# MCU.net
KiCad netlist of a schematic drawn in Altium Designer
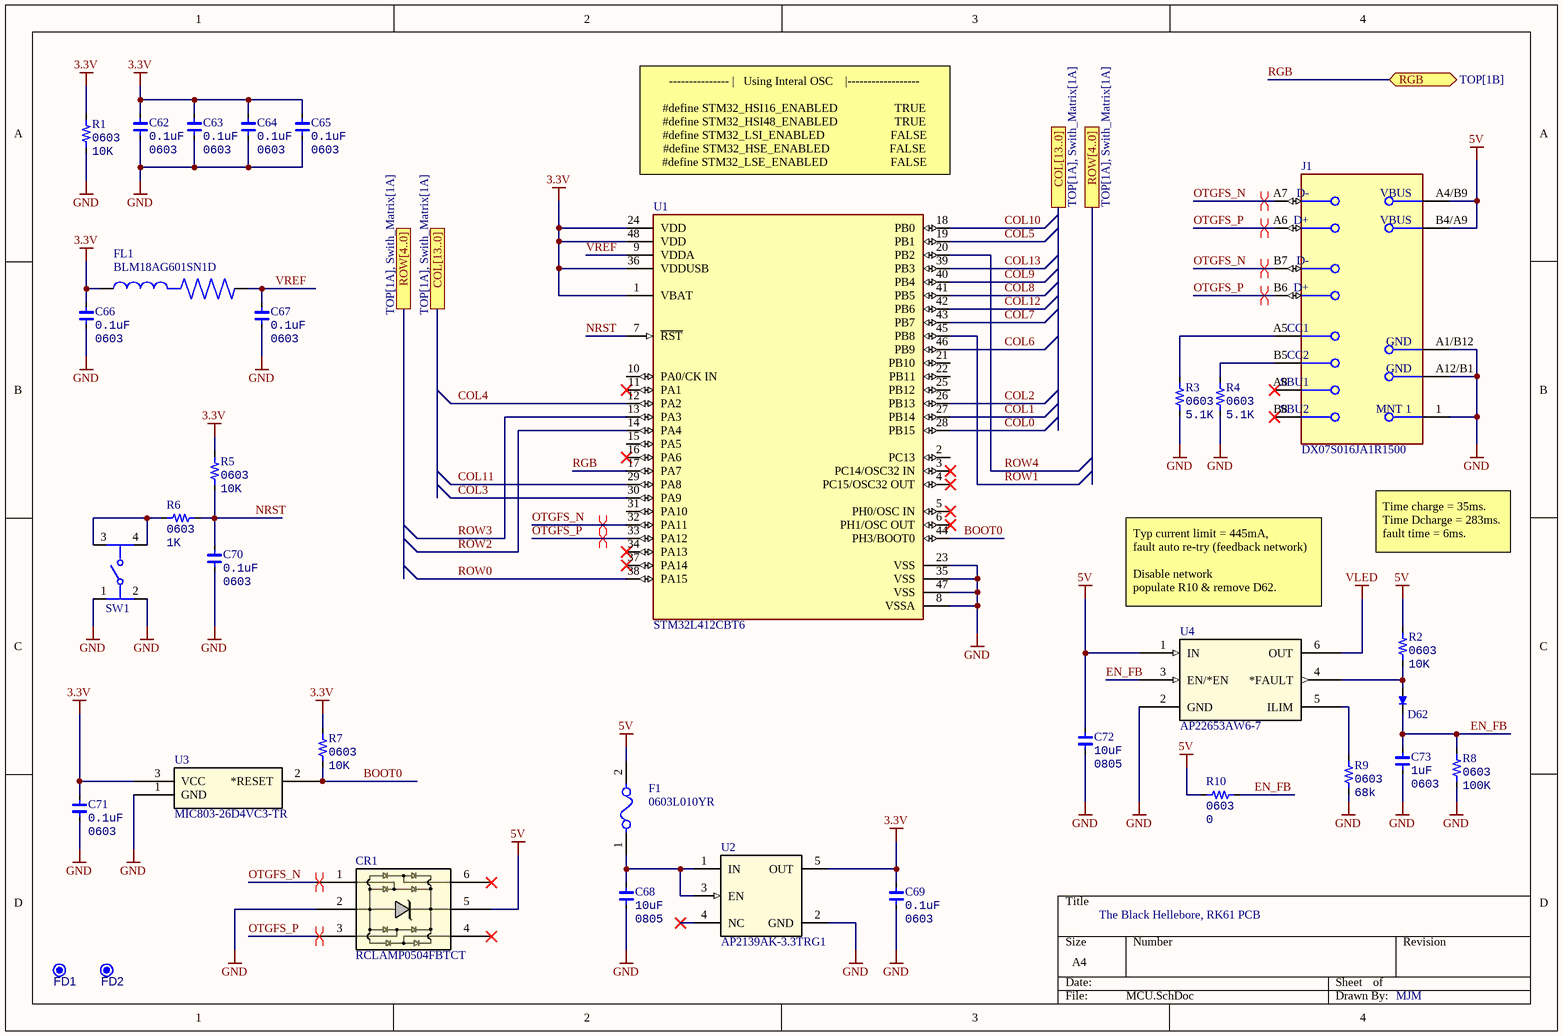
[diagram p0: MCU.SchDoc]

(export (version "E")
  (design (tool "Eeschema 10.0.6"))
  (components
    (comp (ref "C62")
      (value "0.1uF")
      (footprint "FP-CC0603-DA-MFG")
      (description "0603 0.1 uF 50 V ±5 % Tolerance X7R SMT Multilayer Ceramic Capacitor")
      (fields (field (name "TYPE") "0603") (field (name "Comment") "CC0603JRX7R9BB104"))
      (libsource (lib "Microcom Corporation") (part "M_Cap"))
    )
    (comp (ref "C63")
      (value "0.1uF")
      (footprint "FP-CC0603-DA-MFG")
      (description "0603 0.1 uF 50 V ±5 % Tolerance X7R SMT Multilayer Ceramic Capacitor")
      (fields (field (name "TYPE") "0603") (field (name "Comment") "CC0603JRX7R9BB104"))
      (libsource (lib "Microcom Corporation") (part "M_Cap"))
    )
    (comp (ref "C64")
      (value "0.1uF")
      (footprint "FP-CC0603-DA-MFG")
      (description "0603 0.1 uF 50 V ±5 % Tolerance X7R SMT Multilayer Ceramic Capacitor")
      (fields (field (name "TYPE") "0603") (field (name "Comment") "CC0603JRX7R9BB104"))
      (libsource (lib "Microcom Corporation") (part "M_Cap"))
    )
    (comp (ref "C65")
      (value "0.1uF")
      (footprint "FP-CC0603-DA-MFG")
      (description "0603 0.1 uF 50 V ±5 % Tolerance X7R SMT Multilayer Ceramic Capacitor")
      (fields (field (name "TYPE") "0603") (field (name "Comment") "CC0603JRX7R9BB104"))
      (libsource (lib "Microcom Corporation") (part "M_Cap"))
    )
    (comp (ref "C66")
      (value "0.1uF")
      (footprint "FP-CC0603-DA-MFG")
      (description "0603 0.1 uF 50 V ±5 % Tolerance X7R SMT Multilayer Ceramic Capacitor")
      (fields (field (name "TYPE") "0603") (field (name "Comment") "CC0603JRX7R9BB104"))
      (libsource (lib "Microcom Corporation") (part "M_Cap"))
    )
    (comp (ref "C67")
      (value "0.1uF")
      (footprint "FP-CC0603-DA-MFG")
      (description "0603 0.1 uF 50 V ±5 % Tolerance X7R SMT Multilayer Ceramic Capacitor")
      (fields (field (name "TYPE") "0603") (field (name "Comment") "CC0603JRX7R9BB104"))
      (libsource (lib "Microcom Corporation") (part "M_Cap"))
    )
    (comp (ref "C68")
      (value "10uF")
      (footprint "FP-GRM21B-0_15-MFG")
      (description "Cap Ceramic 10uF 10V X7R 10% Pad SMD 0805 125C T/R")
      (fields (field (name "TYPE") "0805") (field (name "Comment") "GRM21BR71A106KA73K"))
      (libsource (lib "Microcom Corporation") (part "M_Cap"))
    )
    (comp (ref "C69")
      (value "0.1uF")
      (footprint "FP-CC0603-DA-MFG")
      (description "0603 0.1 uF 50 V ±5 % Tolerance X7R SMT Multilayer Ceramic Capacitor")
      (fields (field (name "TYPE") "0603") (field (name "Comment") "CC0603JRX7R9BB104"))
      (libsource (lib "Microcom Corporation") (part "M_Cap"))
    )
    (comp (ref "C70")
      (value "0.1uF")
      (footprint "FP-CC0603-DA-MFG")
      (description "0603 0.1 uF 50 V ±5 % Tolerance X7R SMT Multilayer Ceramic Capacitor")
      (fields (field (name "TYPE") "0603") (field (name "Comment") "CC0603JRX7R9BB104"))
      (libsource (lib "Microcom Corporation") (part "M_Cap"))
    )
    (comp (ref "C71")
      (value "0.1uF")
      (footprint "FP-CC0603-DA-MFG")
      (description "0603 0.1 uF 50 V ±5 % Tolerance X7R SMT Multilayer Ceramic Capacitor")
      (fields (field (name "TYPE") "0603") (field (name "Comment") "CC0603JRX7R9BB104"))
      (libsource (lib "Microcom Corporation") (part "M_Cap"))
    )
    (comp (ref "C72")
      (value "10uF")
      (footprint "FP-GRM21B-0_15-MFG")
      (description "Cap Ceramic 10uF 10V X7R 10% Pad SMD 0805 125C T/R")
      (fields (field (name "TYPE") "0805") (field (name "Comment") "GRM21BR71A106KA73K"))
      (libsource (lib "Microcom Corporation") (part "M_Cap"))
    )
    (comp (ref "C73")
      (value "1uF")
      (footprint "FP-CC0603-DA-MFG")
      (description "Cap Ceramic 1uF 16V X7R 5% SMD 0603 125°C Paper T/R")
      (fields (field (name "TYPE") "0603") (field (name "Comment") "CC0603JRX7R7BB105"))
      (libsource (lib "Microcom Corporation") (part "M_Cap"))
    )
    (comp (ref "CR1")
      (value "RCLAMP0504FBTCT")
      (footprint "SC70_RCLAMP_SEM")
      (description "ESD Suppressor TVS Quad Uni-Dir 30kV 6-Pin SC-70 T/R")
      (fields (field (name "COPYRIGHT") "Copyright (C) 2022 Ultra Librarian. All rights reserved."))
      (libsource (lib "Microcom Corporation") (part "RCLAMP0504FBTCT"))
    )
    (comp (ref "D62")
      (value "RB520S30T5G")
      (footprint "ONSC-SOD-523-2-502-01_V")
      (description "RB520S30T5G - 30 V 200 mA Surface Mount Schottky Diode - SOD-523")
      (libsource (lib "Microcom Corporation") (part "ONSC-D-K1A2-2"))
    )
    (comp (ref "F1")
      (value "0603L010YR")
      (footprint "FP-0603L-MFG")
      (description "15VDC 100mA")
      (libsource (lib "Microcom Corporation") (part "5bcf9b9f640e542cf0359d10258e979"))
    )
    (comp (ref "FD1")
      (value "FIDUCIAL")
      (footprint "FID1X2R")
      (description "Fiducial - Round 1x2mm")
      (libsource (lib "Microcom Corporation") (part "CMP-00134-2"))
    )
    (comp (ref "FD2")
      (value "FIDUCIAL")
      (footprint "FID1X2R")
      (description "Fiducial - Round 1x2mm")
      (libsource (lib "Microcom Corporation") (part "CMP-00134-2"))
    )
    (comp (ref "FL1")
      (value "BLM18AG601SN1D")
      (footprint "BEADC1608X95N")
      (description "600 Ohms @ 100MHz 1 Ferrite Bead 0603 _1608 Metric_ 500mA 380mOhm")
      (fields (field (name "DIGI-KEY_PART_NUMBER") "490-1014-1-ND") (field (name "MANUFACTURER") "Murata"))
      (libsource (lib "Microcom Corporation") (part "BLM18AG601SN1D"))
    )
    (comp (ref "J1")
      (value "DX07S016JA1R1500")
      (footprint "FP-DX07S016JA1R1500-MFG")
      (description "Connector, USB Type C Receptacle, 1500 piece reel, 16 Pin Version")
      (libsource (lib "Microcom Corporation") (part "7f3e9989102a0f22bff9cb010881d34"))
    )
    (comp (ref "R1")
      (value "10K")
      (footprint "FP-RMCF0603-MFG")
      (description "Res Thick Film 0603 10K Ohm 5% 1/10W ±100ppm/°C Molded SMD SMD Paper T/R")
      (fields (field (name "TYPE") "0603") (field (name "Comment") "RMCF0603JT10K0"))
      (libsource (lib "Microcom Corporation") (part "M_Res"))
    )
    (comp (ref "R2")
      (value "10K")
      (footprint "FP-RMCF0603-MFG")
      (description "Res Thick Film 0603 10K Ohm 5% 1/10W ±100ppm/°C Molded SMD SMD Paper T/R")
      (fields (field (name "TYPE") "0603") (field (name "Comment") "RMCF0603JT10K0"))
      (libsource (lib "Microcom Corporation") (part "M_Res"))
    )
    (comp (ref "R3")
      (value "5.1K")
      (footprint "FP-RMCF0603-MFG")
      (description "Res Thick Film 0603 5.1K Ohm 5% 1/10W ±200ppm/°C Molded SMD Paper T/R")
      (fields (field (name "TYPE") "0603") (field (name "Comment") "RMCF0603JT5K10"))
      (libsource (lib "Microcom Corporation") (part "M_Res"))
    )
    (comp (ref "R4")
      (value "5.1K")
      (footprint "FP-RMCF0603-MFG")
      (description "Res Thick Film 0603 5.1K Ohm 5% 1/10W ±200ppm/°C Molded SMD Paper T/R")
      (fields (field (name "TYPE") "0603") (field (name "Comment") "RMCF0603JT5K10"))
      (libsource (lib "Microcom Corporation") (part "M_Res"))
    )
    (comp (ref "R5")
      (value "10K")
      (footprint "FP-RMCF0603-MFG")
      (description "Res Thick Film 0603 10K Ohm 5% 1/10W ±100ppm/°C Molded SMD SMD Paper T/R")
      (fields (field (name "TYPE") "0603") (field (name "Comment") "RMCF0603JT10K0"))
      (libsource (lib "Microcom Corporation") (part "M_Res"))
    )
    (comp (ref "R6")
      (value "1K")
      (footprint "FP-RMCF0603-MFG")
      (description "Res Thick Film 0603 1K Ohm 5% 1/10W ±200ppm/°C Molded SMD Paper T/R")
      (fields (field (name "TYPE") "0603") (field (name "Comment") "RMCF0603JT1K00"))
      (libsource (lib "Microcom Corporation") (part "M_Res"))
    )
    (comp (ref "R7")
      (value "10K")
      (footprint "FP-RMCF0603-MFG")
      (description "Res Thick Film 0603 10K Ohm 5% 1/10W ±100ppm/°C Molded SMD SMD Paper T/R")
      (fields (field (name "TYPE") "0603") (field (name "Comment") "RMCF0603JT10K0"))
      (libsource (lib "Microcom Corporation") (part "M_Res"))
    )
    (comp (ref "R8")
      (value "100K")
      (footprint "FP-RMCF0603-MFG")
      (description "Res Thick Film 0603 100K Ohm 5% 1/10W ±200ppm/°C Molded SMD Paper T/R")
      (fields (field (name "TYPE") "0603") (field (name "Comment") "RMCF0603JT100K"))
      (libsource (lib "Microcom Corporation") (part "M_Res"))
    )
    (comp (ref "R9")
      (value "68k")
      (footprint "FP-RMCF0603-MFG")
      (description "Res Thick Film 0603 68K Ohm 1% 0.1W(1/10W) ±100ppm/C Pad SMD Automotive T/R")
      (fields (field (name "TYPE") "0603") (field (name "Comment") "RMCF0603FT68K0"))
      (libsource (lib "Microcom Corporation") (part "M_Res"))
    )
    (comp (ref "R10")
      (value "0")
      (footprint "FP-RMCF0603-MFG")
      (description "Res Thick Film 0603 0 Ohm Jumper 1/10W 100Ppm/ C Smd Rohs Compliant: Yes")
      (fields (field (name "TYPE") "0603") (field (name "Comment") "RMCF0603ZT0R00"))
      (libsource (lib "Microcom Corporation") (part "M_Res"))
    )
    (comp (ref "SW1")
      (value "PTS526SK15SMTR2LFS")
      (footprint "FP-PTS526SK15SMTR2LFS-MFG")
      (description "Switch Tactile N.O. SPST Round Button Gull Wing 0.05A 12VDC 200000Cycles 2.55N SMD T/R")
      (libsource (lib "Microcom Corporation") (part "b8895f3f4cefb76e1819d2863dba89b"))
    )
    (comp (ref "U1")
      (value "STM32L412CBT6")
      (footprint "FP-LQFP48-5B-MFG")
      (libsource (lib "Microcom Corporation") (part "4ca86e70463fb043fbe0a04138c23db"))
    )
    (comp (ref "U2")
      (value "AP2139AK-3.3TRG1")
      (footprint "DBV0005A-IPC_A")
      (description "IC REG LDO 3.3V 0.25A SOT25")
      (libsource (lib "Microcom Corporation") (part "AP2139AK-3.3TRG1"))
    )
    (comp (ref "U3")
      (value "MIC803-26D4VC3-TR")
      (footprint "SC-70_C3_MCH")
      (description "3-Pin Microprocessor Supervisor Circuit w/ Open-Drain Reset Output")
      (fields (field (name "COPYRIGHT") "Copyright (C) 2022 Ultra Librarian. All rights reserved."))
      (libsource (lib "Microcom Corporation") (part "MIC803-26D4VC3-TR"))
    )
    (comp (ref "U4")
      (value "AP22653AW6-7")
      (footprint "SOT26-A1_DIO")
      (description "PRECISION ADJUSTABLE CURRENT-LIMITED POWER SWITCHES, -40 to 85°C pF, RoHS")
      (fields (field (name "COPYRIGHT") "Copyright (C) 2022 Ultra Librarian. All rights reserved."))
      (libsource (lib "Microcom Corporation") (part "AP22653AW6-7"))
    )
  )
  (nets
    (net (code "1") (name "/BOOT0") (class "Default")
      (node (ref "R7") (pin "1") (pinfunction "1_1") (pintype "passive"))
      (node (ref "U1") (pin "44") (pinfunction "PH3/BOOT0_44") (pintype "bidirectional"))
      (node (ref "U3") (pin "2") (pinfunction "*RESET_2") (pintype "passive"))
    )
    (net (code "2") (name "/COL0") (class "Default")
      (node (ref "U1") (pin "28") (pinfunction "PB15_28") (pintype "bidirectional"))
    )
    (net (code "3") (name "/COL1") (class "Default")
      (node (ref "U1") (pin "27") (pinfunction "PB14_27") (pintype "bidirectional"))
    )
    (net (code "4") (name "/COL2") (class "Default")
      (node (ref "U1") (pin "26") (pinfunction "PB13_26") (pintype "bidirectional"))
    )
    (net (code "5") (name "/COL3") (class "Default")
      (node (ref "U1") (pin "30") (pinfunction "PA9_30") (pintype "bidirectional"))
    )
    (net (code "6") (name "/COL4") (class "Default")
      (node (ref "U1") (pin "12") (pinfunction "PA2_12") (pintype "bidirectional"))
    )
    (net (code "7") (name "/COL5") (class "Default")
      (node (ref "U1") (pin "19") (pinfunction "PB1_19") (pintype "bidirectional"))
    )
    (net (code "8") (name "/COL6") (class "Default")
      (node (ref "U1") (pin "46") (pinfunction "PB9_46") (pintype "bidirectional"))
    )
    (net (code "9") (name "/COL7") (class "Default")
      (node (ref "U1") (pin "43") (pinfunction "PB7_43") (pintype "bidirectional"))
    )
    (net (code "10") (name "/COL8") (class "Default")
      (node (ref "U1") (pin "41") (pinfunction "PB5_41") (pintype "bidirectional"))
    )
    (net (code "11") (name "/COL9") (class "Default")
      (node (ref "U1") (pin "40") (pinfunction "PB4_40") (pintype "bidirectional"))
    )
    (net (code "12") (name "/COL10") (class "Default")
      (node (ref "U1") (pin "18") (pinfunction "PB0_18") (pintype "bidirectional"))
    )
    (net (code "13") (name "/COL11") (class "Default")
      (node (ref "U1") (pin "29") (pinfunction "PA8_29") (pintype "bidirectional"))
    )
    (net (code "14") (name "/COL12") (class "Default")
      (node (ref "U1") (pin "42") (pinfunction "PB6_42") (pintype "bidirectional"))
    )
    (net (code "15") (name "/COL13") (class "Default")
      (node (ref "U1") (pin "39") (pinfunction "PB3_39") (pintype "bidirectional"))
    )
    (net (code "17") (name "/EN_FB") (class "Default")
      (node (ref "C73") (pin "2") (pinfunction "2_2") (pintype "passive"))
      (node (ref "D62") (pin "1") (pinfunction "K_1") (pintype "passive"))
      (node (ref "R10") (pin "2") (pinfunction "2_2") (pintype "passive"))
      (node (ref "R8") (pin "2") (pinfunction "2_2") (pintype "passive"))
      (node (ref "U4") (pin "3") (pinfunction "EN/*EN_3") (pintype "input"))
    )
    (net (code "18") (name "/NRST") (class "Default")
      (node (ref "C70") (pin "2") (pinfunction "2_2") (pintype "passive"))
      (node (ref "R5") (pin "1") (pinfunction "1_1") (pintype "passive"))
      (node (ref "R6") (pin "1") (pinfunction "1_1") (pintype "passive"))
      (node (ref "U1") (pin "7") (pinfunction "~{RST}_7") (pintype "input"))
    )
    (net (code "19") (name "/OTGFS_N") (class "Default")
      (node (ref "CR1") (pin "1") (pinfunction "1_1") (pintype "passive"))
      (node (ref "J1") (pin "A7") (pinfunction "D-_A7") (pintype "bidirectional"))
      (node (ref "J1") (pin "B7") (pinfunction "D-_B7") (pintype "bidirectional"))
      (node (ref "U1") (pin "32") (pinfunction "PA11_32") (pintype "bidirectional"))
    )
    (net (code "20") (name "/OTGFS_P") (class "Default")
      (node (ref "CR1") (pin "3") (pinfunction "3_3") (pintype "passive"))
      (node (ref "J1") (pin "A6") (pinfunction "D+_A6") (pintype "bidirectional"))
      (node (ref "J1") (pin "B6") (pinfunction "D+_B6") (pintype "bidirectional"))
      (node (ref "U1") (pin "33") (pinfunction "PA12_33") (pintype "bidirectional"))
    )
    (net (code "21") (name "/RGB") (class "Default")
      (node (ref "U1") (pin "17") (pinfunction "PA7_17") (pintype "bidirectional"))
    )
    (net (code "22") (name "/ROW0") (class "Default")
      (node (ref "U1") (pin "38") (pinfunction "PA15_38") (pintype "bidirectional"))
    )
    (net (code "23") (name "/ROW1") (class "Default")
      (node (ref "U1") (pin "45") (pinfunction "PB8_45") (pintype "bidirectional"))
    )
    (net (code "24") (name "/ROW2") (class "Default")
      (node (ref "U1") (pin "14") (pinfunction "PA4_14") (pintype "bidirectional"))
    )
    (net (code "25") (name "/ROW3") (class "Default")
      (node (ref "U1") (pin "13") (pinfunction "PA3_13") (pintype "bidirectional"))
    )
    (net (code "26") (name "/ROW4") (class "Default")
      (node (ref "U1") (pin "20") (pinfunction "PB2_20") (pintype "bidirectional"))
    )
    (net (code "28") (name "/VREF") (class "Default")
      (node (ref "C67") (pin "2") (pinfunction "2_2") (pintype "passive"))
      (node (ref "FL1") (pin "2") (pinfunction "2_2") (pintype "passive"))
      (node (ref "U1") (pin "9") (pinfunction "VDDA_9") (pintype "power_in"))
    )
    (net (code "29") (name "3.3V") (class "Default")
      (node (ref "C62") (pin "2") (pinfunction "2_2") (pintype "passive"))
      (node (ref "C63") (pin "2") (pinfunction "2_2") (pintype "passive"))
      (node (ref "C64") (pin "2") (pinfunction "2_2") (pintype "passive"))
      (node (ref "C65") (pin "2") (pinfunction "2_2") (pintype "passive"))
      (node (ref "C66") (pin "2") (pinfunction "2_2") (pintype "passive"))
      (node (ref "C69") (pin "2") (pinfunction "2_2") (pintype "passive"))
      (node (ref "C71") (pin "2") (pinfunction "2_2") (pintype "passive"))
      (node (ref "FL1") (pin "1") (pinfunction "1_1") (pintype "passive"))
      (node (ref "R1") (pin "2") (pinfunction "2_2") (pintype "passive"))
      (node (ref "R5") (pin "2") (pinfunction "2_2") (pintype "passive"))
      (node (ref "R7") (pin "2") (pinfunction "2_2") (pintype "passive"))
      (node (ref "U1") (pin "1") (pinfunction "VBAT_1") (pintype "power_in"))
      (node (ref "U1") (pin "24") (pinfunction "VDD_24") (pintype "power_in"))
      (node (ref "U1") (pin "36") (pinfunction "VDDUSB_36") (pintype "power_in"))
      (node (ref "U1") (pin "48") (pinfunction "VDD_48") (pintype "power_in"))
      (node (ref "U2") (pin "5") (pinfunction "OUT_5") (pintype "passive"))
      (node (ref "U3") (pin "3") (pinfunction "VCC_3") (pintype "power_in"))
    )
    (net (code "30") (name "5V") (class "Default")
      (node (ref "C72") (pin "2") (pinfunction "2_2") (pintype "passive"))
      (node (ref "CR1") (pin "5") (pinfunction "5_5") (pintype "passive"))
      (node (ref "F1") (pin "2") (pinfunction "2_2") (pintype "passive"))
      (node (ref "J1") (pin "A4/B9") (pinfunction "VBUS_A4/B9") (pintype "power_in"))
      (node (ref "J1") (pin "B4/A9") (pinfunction "VBUS_B4/A9") (pintype "power_in"))
      (node (ref "R10") (pin "1") (pinfunction "1_1") (pintype "passive"))
      (node (ref "R2") (pin "2") (pinfunction "2_2") (pintype "passive"))
      (node (ref "U4") (pin "1") (pinfunction "IN_1") (pintype "input"))
    )
    (net (code "31") (name "GND") (class "Default")
      (node (ref "C62") (pin "1") (pinfunction "1_1") (pintype "passive"))
      (node (ref "C63") (pin "1") (pinfunction "1_1") (pintype "passive"))
      (node (ref "C64") (pin "1") (pinfunction "1_1") (pintype "passive"))
      (node (ref "C65") (pin "1") (pinfunction "1_1") (pintype "passive"))
      (node (ref "C66") (pin "1") (pinfunction "1_1") (pintype "passive"))
      (node (ref "C67") (pin "1") (pinfunction "1_1") (pintype "passive"))
      (node (ref "C68") (pin "1") (pinfunction "1_1") (pintype "passive"))
      (node (ref "C69") (pin "1") (pinfunction "1_1") (pintype "passive"))
      (node (ref "C70") (pin "1") (pinfunction "1_1") (pintype "passive"))
      (node (ref "C71") (pin "1") (pinfunction "1_1") (pintype "passive"))
      (node (ref "C72") (pin "1") (pinfunction "1_1") (pintype "passive"))
      (node (ref "C73") (pin "1") (pinfunction "1_1") (pintype "passive"))
      (node (ref "CR1") (pin "2") (pinfunction "2_2") (pintype "passive"))
      (node (ref "J1") (pin "1") (pinfunction "MNT_1_1") (pintype "passive"))
      (node (ref "J1") (pin "A1/B12") (pinfunction "GND_A1/B12") (pintype "power_in"))
      (node (ref "J1") (pin "A12/B1") (pinfunction "GND_A12/B1") (pintype "power_in"))
      (node (ref "R1") (pin "1") (pinfunction "1_1") (pintype "passive"))
      (node (ref "R3") (pin "1") (pinfunction "1_1") (pintype "passive"))
      (node (ref "R4") (pin "1") (pinfunction "1_1") (pintype "passive"))
      (node (ref "R8") (pin "1") (pinfunction "1_1") (pintype "passive"))
      (node (ref "R9") (pin "1") (pinfunction "1_1") (pintype "passive"))
      (node (ref "SW1") (pin "1") (pinfunction "1_1") (pintype "passive"))
      (node (ref "SW1") (pin "2") (pinfunction "2_2") (pintype "passive"))
      (node (ref "U1") (pin "23") (pinfunction "VSS_23") (pintype "power_in"))
      (node (ref "U1") (pin "35") (pinfunction "VSS_35") (pintype "power_in"))
      (node (ref "U1") (pin "47") (pinfunction "VSS_47") (pintype "power_in"))
      (node (ref "U1") (pin "8") (pinfunction "VSSA_8") (pintype "power_in"))
      (node (ref "U2") (pin "2") (pinfunction "GND_2") (pintype "power_in"))
      (node (ref "U3") (pin "1") (pinfunction "GND_1") (pintype "power_in"))
      (node (ref "U4") (pin "2") (pinfunction "GND_2") (pintype "passive"))
    )
    (net (code "32") (name "Net-(D62-A)") (class "Default")
      (node (ref "D62") (pin "2") (pinfunction "A_2") (pintype "passive"))
      (node (ref "R2") (pin "1") (pinfunction "1_1") (pintype "passive"))
      (node (ref "U4") (pin "4") (pinfunction "*FAULT_4") (pintype "output"))
    )
    (net (code "33") (name "Net-(J1-CC1)") (class "Default")
      (node (ref "J1") (pin "A5") (pinfunction "CC1_A5") (pintype "passive"))
      (node (ref "R3") (pin "2") (pinfunction "2_2") (pintype "passive"))
    )
    (net (code "34") (name "Net-(J1-CC2)") (class "Default")
      (node (ref "J1") (pin "B5") (pinfunction "CC2_B5") (pintype "passive"))
      (node (ref "R4") (pin "2") (pinfunction "2_2") (pintype "passive"))
    )
    (net (code "35") (name "Net-(R6-Pad2)") (class "Default")
      (node (ref "R6") (pin "2") (pinfunction "2_2") (pintype "passive"))
      (node (ref "SW1") (pin "3") (pinfunction "3_3") (pintype "passive"))
      (node (ref "SW1") (pin "4") (pinfunction "4_4") (pintype "passive"))
    )
    (net (code "36") (name "Net-(U2-EN)") (class "Default")
      (node (ref "C68") (pin "2") (pinfunction "2_2") (pintype "passive"))
      (node (ref "F1") (pin "1") (pinfunction "1_1") (pintype "passive"))
      (node (ref "U2") (pin "1") (pinfunction "IN_1") (pintype "power_in"))
      (node (ref "U2") (pin "3") (pinfunction "EN_3") (pintype "input"))
    )
    (net (code "37") (name "Net-(U4-ILIM)") (class "Default")
      (node (ref "R9") (pin "2") (pinfunction "2_2") (pintype "passive"))
      (node (ref "U4") (pin "5") (pinfunction "ILIM_5") (pintype "passive"))
    )
    (net (code "38") (name "VLED") (class "Default")
      (node (ref "U4") (pin "6") (pinfunction "OUT_6") (pintype "passive"))
    )
    (net (code "39") (name "unconnected-(CR1-Pad4)") (class "Default")
      (node (ref "CR1") (pin "4") (pinfunction "4_4") (pintype "passive+no_connect"))
    )
    (net (code "40") (name "unconnected-(CR1-Pad6)") (class "Default")
      (node (ref "CR1") (pin "6") (pinfunction "6_6") (pintype "passive+no_connect"))
    )
    (net (code "41") (name "unconnected-(J1-SBU1-PadA8)") (class "Default")
      (node (ref "J1") (pin "A8") (pinfunction "SBU1_A8") (pintype "passive+no_connect"))
    )
    (net (code "42") (name "unconnected-(J1-SBU2-PadB8)") (class "Default")
      (node (ref "J1") (pin "B8") (pinfunction "SBU2_B8") (pintype "passive+no_connect"))
    )
    (net (code "43") (name "unconnected-(U1-PA0{slash}CK_IN-Pad10)") (class "Default")
      (node (ref "U1") (pin "10") (pinfunction "PA0/CK_IN_10") (pintype "bidirectional"))
    )
    (net (code "44") (name "unconnected-(U1-PA1-Pad11)") (class "Default")
      (node (ref "U1") (pin "11") (pinfunction "PA1_11") (pintype "bidirectional+no_connect"))
    )
    (net (code "45") (name "unconnected-(U1-PA5-Pad15)") (class "Default")
      (node (ref "U1") (pin "15") (pinfunction "PA5_15") (pintype "bidirectional"))
    )
    (net (code "46") (name "unconnected-(U1-PA6-Pad16)") (class "Default")
      (node (ref "U1") (pin "16") (pinfunction "PA6_16") (pintype "bidirectional+no_connect"))
    )
    (net (code "47") (name "unconnected-(U1-PA10-Pad31)") (class "Default")
      (node (ref "U1") (pin "31") (pinfunction "PA10_31") (pintype "bidirectional"))
    )
    (net (code "48") (name "unconnected-(U1-PA13-Pad34)") (class "Default")
      (node (ref "U1") (pin "34") (pinfunction "PA13_34") (pintype "bidirectional+no_connect"))
    )
    (net (code "49") (name "unconnected-(U1-PA14-Pad37)") (class "Default")
      (node (ref "U1") (pin "37") (pinfunction "PA14_37") (pintype "bidirectional+no_connect"))
    )
    (net (code "50") (name "unconnected-(U1-PB10-Pad21)") (class "Default")
      (node (ref "U1") (pin "21") (pinfunction "PB10_21") (pintype "bidirectional"))
    )
    (net (code "51") (name "unconnected-(U1-PB11-Pad22)") (class "Default")
      (node (ref "U1") (pin "22") (pinfunction "PB11_22") (pintype "bidirectional"))
    )
    (net (code "52") (name "unconnected-(U1-PB12-Pad25)") (class "Default")
      (node (ref "U1") (pin "25") (pinfunction "PB12_25") (pintype "bidirectional"))
    )
    (net (code "53") (name "unconnected-(U1-PC13-Pad2)") (class "Default")
      (node (ref "U1") (pin "2") (pinfunction "PC13_2") (pintype "bidirectional"))
    )
    (net (code "54") (name "unconnected-(U1-PC14{slash}OSC32_IN-Pad3)") (class "Default")
      (node (ref "U1") (pin "3") (pinfunction "PC14/OSC32_IN_3") (pintype "bidirectional+no_connect"))
    )
    (net (code "55") (name "unconnected-(U1-PC15{slash}OSC32_OUT-Pad4)") (class "Default")
      (node (ref "U1") (pin "4") (pinfunction "PC15/OSC32_OUT_4") (pintype "bidirectional+no_connect"))
    )
    (net (code "56") (name "unconnected-(U1-PH0{slash}OSC_IN-Pad5)") (class "Default")
      (node (ref "U1") (pin "5") (pinfunction "PH0/OSC_IN_5") (pintype "bidirectional+no_connect"))
    )
    (net (code "57") (name "unconnected-(U1-PH1{slash}OSC_OUT-Pad6)") (class "Default")
      (node (ref "U1") (pin "6") (pinfunction "PH1/OSC_OUT_6") (pintype "bidirectional+no_connect"))
    )
    (net (code "58") (name "unconnected-(U2-NC-Pad4)") (class "Default")
      (node (ref "U2") (pin "4") (pinfunction "NC_4") (pintype "passive+no_connect"))
    )
  )
)
